# Digital_Input3.net
KiCad netlist of a schematic drawn in Altium Designer
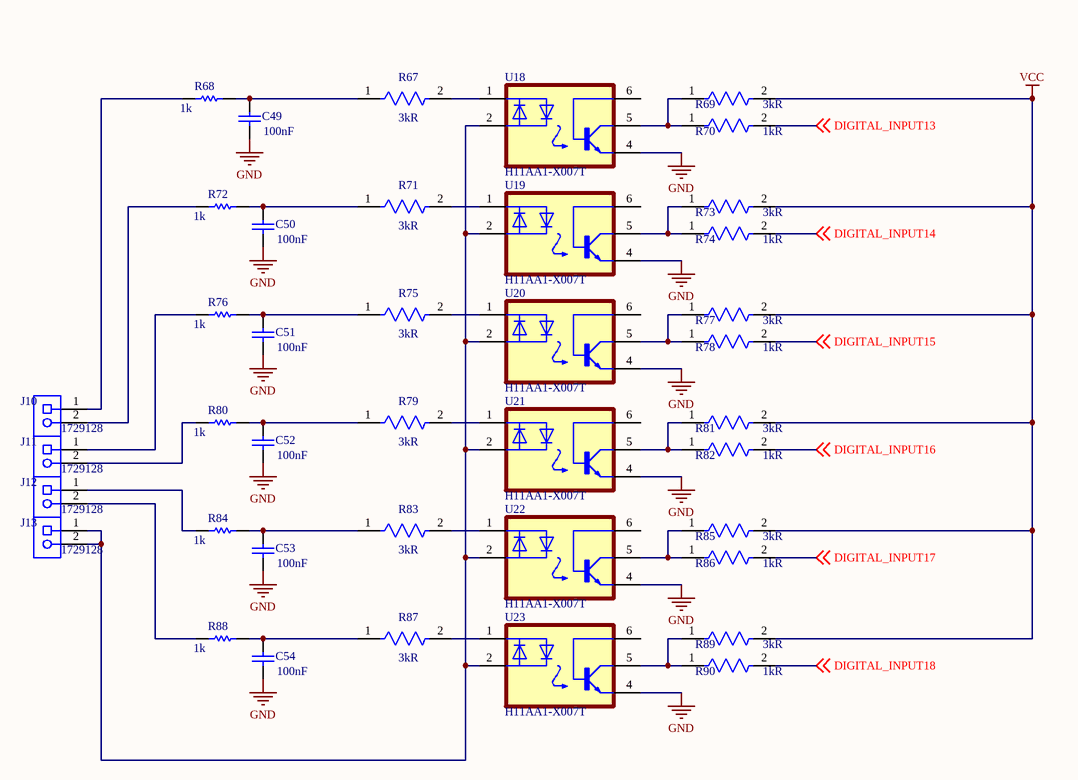
[diagram p0: Digital_Input3.SchDoc]

(export (version "E")
  (design (tool "Eeschema 10.0.6"))
  (components
    (comp (ref "C49")
      (value "100nF")
      (footprint "CAPC1608X87X35NL15T15")
      (fields (field (name "MANUFACTURER") "Kemet") (field (name "PART NUMBER") "C0603T104K3RACTU"))
      (libsource (lib "Altium Content Vault") (part "CAP"))
    )
    (comp (ref "C50")
      (value "100nF")
      (footprint "CAPC1608X87X35NL15T15")
      (fields (field (name "MANUFACTURER") "Kemet") (field (name "PART NUMBER") "C0603T104K3RACTU"))
      (libsource (lib "Altium Content Vault") (part "CAP"))
    )
    (comp (ref "C51")
      (value "100nF")
      (footprint "CAPC1608X87X35NL15T15")
      (fields (field (name "MANUFACTURER") "Kemet") (field (name "PART NUMBER") "C0603T104K3RACTU"))
      (libsource (lib "Altium Content Vault") (part "CAP"))
    )
    (comp (ref "C52")
      (value "100nF")
      (footprint "CAPC1608X87X35NL15T15")
      (fields (field (name "MANUFACTURER") "Kemet") (field (name "PART NUMBER") "C0603T104K3RACTU"))
      (libsource (lib "Altium Content Vault") (part "CAP"))
    )
    (comp (ref "C53")
      (value "100nF")
      (footprint "CAPC1608X87X35NL15T15")
      (fields (field (name "MANUFACTURER") "Kemet") (field (name "PART NUMBER") "C0603T104K3RACTU"))
      (libsource (lib "Altium Content Vault") (part "CAP"))
    )
    (comp (ref "C54")
      (value "100nF")
      (footprint "CAPC1608X87X35NL15T15")
      (fields (field (name "MANUFACTURER") "Kemet") (field (name "PART NUMBER") "C0603T104K3RACTU"))
      (libsource (lib "Altium Content Vault") (part "CAP"))
    )
    (comp (ref "J10")
      (value "1729128")
      (footprint "PHOE-1729128-2_V")
      (description "PCB Terminal Block, 13.5 A, 400 V, 2-Pin THD, RoHS, Bulk")
      (fields (field (name "MANUFACTURER") "Phoenix Contact"))
      (libsource (lib "Altium Content Vault") (part "CN-2P-F-R2"))
    )
    (comp (ref "J11")
      (value "1729128")
      (footprint "PHOE-1729128-2_V")
      (description "PCB Terminal Block, 13.5 A, 400 V, 2-Pin THD, RoHS, Bulk")
      (fields (field (name "MANUFACTURER") "Phoenix Contact"))
      (libsource (lib "Altium Content Vault") (part "CN-2P-F-R2"))
    )
    (comp (ref "J12")
      (value "1729128")
      (footprint "PHOE-1729128-2_V")
      (description "PCB Terminal Block, 13.5 A, 400 V, 2-Pin THD, RoHS, Bulk")
      (fields (field (name "MANUFACTURER") "Phoenix Contact"))
      (libsource (lib "Altium Content Vault") (part "CN-2P-F-R2"))
    )
    (comp (ref "J13")
      (value "1729128")
      (footprint "PHOE-1729128-2_V")
      (description "PCB Terminal Block, 13.5 A, 400 V, 2-Pin THD, RoHS, Bulk")
      (fields (field (name "MANUFACTURER") "Phoenix Contact"))
      (libsource (lib "Altium Content Vault") (part "CN-2P-F-R2"))
    )
    (comp (ref "R67")
      (value "CRCW06033K00FKEA")
      (footprint "FP-CRCW0603-e3-IPC_A")
      (description "RES Thick Film, 3kΩ, 1%, 0.1W, 100ppm/°C, 0603")
      (fields (field (name "RESISTANCE") "3kR") (field (name "TOLERANCE") "1%"))
      (libsource (lib "Altium Content Vault") (part "1029c3af85768c4190bb7ad29bc67b5"))
    )
    (comp (ref "R68")
      (value "1k")
      (footprint "RESC1608X55X25LL10T15")
      (fields (field (name "PART NUMBER") "RT0603DRE071KL") (field (name "MANUFACTURER") "Yageo"))
      (libsource (lib "Altium Content Vault") (part "RES"))
    )
    (comp (ref "R69")
      (value "CRCW06033K00FKEA")
      (footprint "FP-CRCW0603-e3-IPC_A")
      (description "RES Thick Film, 3kΩ, 1%, 0.1W, 100ppm/°C, 0603")
      (fields (field (name "RESISTANCE") "3kR") (field (name "TOLERANCE") "1%"))
      (libsource (lib "Altium Content Vault") (part "1029c3af85768c4190bb7ad29bc67b5"))
    )
    (comp (ref "R70")
      (value "RC0603FR-071KL")
      (footprint "FP-RC0603-0_55-IPC_C")
      (description "RES 1K OHM 1% 1/10W 0603")
      (fields (field (name "RESISTANCE") "1kR") (field (name "TOLERANCE") "1%"))
      (libsource (lib "Altium Content Vault") (part "1029c3af85768c4190bb7ad29bc67b5"))
    )
    (comp (ref "R71")
      (value "CRCW06033K00FKEA")
      (footprint "FP-CRCW0603-e3-IPC_A")
      (description "RES Thick Film, 3kΩ, 1%, 0.1W, 100ppm/°C, 0603")
      (fields (field (name "RESISTANCE") "3kR") (field (name "TOLERANCE") "1%"))
      (libsource (lib "Altium Content Vault") (part "1029c3af85768c4190bb7ad29bc67b5"))
    )
    (comp (ref "R72")
      (value "1k")
      (footprint "RESC1608X55X25LL10T15")
      (fields (field (name "PART NUMBER") "RT0603DRE071KL") (field (name "MANUFACTURER") "Yageo"))
      (libsource (lib "Altium Content Vault") (part "RES"))
    )
    (comp (ref "R73")
      (value "CRCW06033K00FKEA")
      (footprint "FP-CRCW0603-e3-IPC_A")
      (description "RES Thick Film, 3kΩ, 1%, 0.1W, 100ppm/°C, 0603")
      (fields (field (name "RESISTANCE") "3kR") (field (name "TOLERANCE") "1%"))
      (libsource (lib "Altium Content Vault") (part "1029c3af85768c4190bb7ad29bc67b5"))
    )
    (comp (ref "R74")
      (value "RC0603FR-071KL")
      (footprint "FP-RC0603-0_55-IPC_C")
      (description "RES 1K OHM 1% 1/10W 0603")
      (fields (field (name "RESISTANCE") "1kR") (field (name "TOLERANCE") "1%"))
      (libsource (lib "Altium Content Vault") (part "1029c3af85768c4190bb7ad29bc67b5"))
    )
    (comp (ref "R75")
      (value "CRCW06033K00FKEA")
      (footprint "FP-CRCW0603-e3-IPC_A")
      (description "RES Thick Film, 3kΩ, 1%, 0.1W, 100ppm/°C, 0603")
      (fields (field (name "RESISTANCE") "3kR") (field (name "TOLERANCE") "1%"))
      (libsource (lib "Altium Content Vault") (part "1029c3af85768c4190bb7ad29bc67b5"))
    )
    (comp (ref "R76")
      (value "1k")
      (footprint "RESC1608X55X25LL10T15")
      (fields (field (name "PART NUMBER") "RT0603DRE071KL") (field (name "MANUFACTURER") "Yageo"))
      (libsource (lib "Altium Content Vault") (part "RES"))
    )
    (comp (ref "R77")
      (value "CRCW06033K00FKEA")
      (footprint "FP-CRCW0603-e3-IPC_A")
      (description "RES Thick Film, 3kΩ, 1%, 0.1W, 100ppm/°C, 0603")
      (fields (field (name "RESISTANCE") "3kR") (field (name "TOLERANCE") "1%"))
      (libsource (lib "Altium Content Vault") (part "1029c3af85768c4190bb7ad29bc67b5"))
    )
    (comp (ref "R78")
      (value "RC0603FR-071KL")
      (footprint "FP-RC0603-0_55-IPC_C")
      (description "RES 1K OHM 1% 1/10W 0603")
      (fields (field (name "RESISTANCE") "1kR") (field (name "TOLERANCE") "1%"))
      (libsource (lib "Altium Content Vault") (part "1029c3af85768c4190bb7ad29bc67b5"))
    )
    (comp (ref "R79")
      (value "CRCW06033K00FKEA")
      (footprint "FP-CRCW0603-e3-IPC_A")
      (description "RES Thick Film, 3kΩ, 1%, 0.1W, 100ppm/°C, 0603")
      (fields (field (name "RESISTANCE") "3kR") (field (name "TOLERANCE") "1%"))
      (libsource (lib "Altium Content Vault") (part "1029c3af85768c4190bb7ad29bc67b5"))
    )
    (comp (ref "R80")
      (value "1k")
      (footprint "RESC1608X55X25LL10T15")
      (fields (field (name "PART NUMBER") "RT0603DRE071KL") (field (name "MANUFACTURER") "Yageo"))
      (libsource (lib "Altium Content Vault") (part "RES"))
    )
    (comp (ref "R81")
      (value "CRCW06033K00FKEA")
      (footprint "FP-CRCW0603-e3-IPC_A")
      (description "RES Thick Film, 3kΩ, 1%, 0.1W, 100ppm/°C, 0603")
      (fields (field (name "RESISTANCE") "3kR") (field (name "TOLERANCE") "1%"))
      (libsource (lib "Altium Content Vault") (part "1029c3af85768c4190bb7ad29bc67b5"))
    )
    (comp (ref "R82")
      (value "RC0603FR-071KL")
      (footprint "FP-RC0603-0_55-IPC_C")
      (description "RES 1K OHM 1% 1/10W 0603")
      (fields (field (name "RESISTANCE") "1kR") (field (name "TOLERANCE") "1%"))
      (libsource (lib "Altium Content Vault") (part "1029c3af85768c4190bb7ad29bc67b5"))
    )
    (comp (ref "R83")
      (value "CRCW06033K00FKEA")
      (footprint "FP-CRCW0603-e3-IPC_A")
      (description "RES Thick Film, 3kΩ, 1%, 0.1W, 100ppm/°C, 0603")
      (fields (field (name "RESISTANCE") "3kR") (field (name "TOLERANCE") "1%"))
      (libsource (lib "Altium Content Vault") (part "1029c3af85768c4190bb7ad29bc67b5"))
    )
    (comp (ref "R84")
      (value "1k")
      (footprint "RESC1608X55X25LL10T15")
      (fields (field (name "PART NUMBER") "RT0603DRE071KL") (field (name "MANUFACTURER") "Yageo"))
      (libsource (lib "Altium Content Vault") (part "RES"))
    )
    (comp (ref "R85")
      (value "CRCW06033K00FKEA")
      (footprint "FP-CRCW0603-e3-IPC_A")
      (description "RES Thick Film, 3kΩ, 1%, 0.1W, 100ppm/°C, 0603")
      (fields (field (name "RESISTANCE") "3kR") (field (name "TOLERANCE") "1%"))
      (libsource (lib "Altium Content Vault") (part "1029c3af85768c4190bb7ad29bc67b5"))
    )
    (comp (ref "R86")
      (value "RC0603FR-071KL")
      (footprint "FP-RC0603-0_55-IPC_C")
      (description "RES 1K OHM 1% 1/10W 0603")
      (fields (field (name "RESISTANCE") "1kR") (field (name "TOLERANCE") "1%"))
      (libsource (lib "Altium Content Vault") (part "1029c3af85768c4190bb7ad29bc67b5"))
    )
    (comp (ref "R87")
      (value "CRCW06033K00FKEA")
      (footprint "FP-CRCW0603-e3-IPC_A")
      (description "RES Thick Film, 3kΩ, 1%, 0.1W, 100ppm/°C, 0603")
      (fields (field (name "RESISTANCE") "3kR") (field (name "TOLERANCE") "1%"))
      (libsource (lib "Altium Content Vault") (part "1029c3af85768c4190bb7ad29bc67b5"))
    )
    (comp (ref "R88")
      (value "1k")
      (footprint "RESC1608X55X25LL10T15")
      (fields (field (name "PART NUMBER") "RT0603DRE071KL") (field (name "MANUFACTURER") "Yageo"))
      (libsource (lib "Altium Content Vault") (part "RES"))
    )
    (comp (ref "R89")
      (value "CRCW06033K00FKEA")
      (footprint "FP-CRCW0603-e3-IPC_A")
      (description "RES Thick Film, 3kΩ, 1%, 0.1W, 100ppm/°C, 0603")
      (fields (field (name "RESISTANCE") "3kR") (field (name "TOLERANCE") "1%"))
      (libsource (lib "Altium Content Vault") (part "1029c3af85768c4190bb7ad29bc67b5"))
    )
    (comp (ref "R90")
      (value "RC0603FR-071KL")
      (footprint "FP-RC0603-0_55-IPC_C")
      (description "RES 1K OHM 1% 1/10W 0603")
      (fields (field (name "RESISTANCE") "1kR") (field (name "TOLERANCE") "1%"))
      (libsource (lib "Altium Content Vault") (part "1029c3af85768c4190bb7ad29bc67b5"))
    )
    (comp (ref "U18")
      (value "H11AA1-X007T")
      (footprint "SOIC254P1030X460-6N")
      (description "H11AA1 Series Single Channel 30V 5300 Vrms SMT Phototransistor Optocoupler DIP-6")
      (fields (field (name "MF") "Vishay Semiconductor"))
      (libsource (lib "H11AA1-X007T") (part "H11AA1-X007T"))
    )
    (comp (ref "U19")
      (value "H11AA1-X007T")
      (footprint "SOIC254P1030X460-6N")
      (description "H11AA1 Series Single Channel 30V 5300 Vrms SMT Phototransistor Optocoupler DIP-6")
      (fields (field (name "MF") "Vishay Semiconductor"))
      (libsource (lib "H11AA1-X007T") (part "H11AA1-X007T"))
    )
    (comp (ref "U20")
      (value "H11AA1-X007T")
      (footprint "SOIC254P1030X460-6N")
      (description "H11AA1 Series Single Channel 30V 5300 Vrms SMT Phototransistor Optocoupler DIP-6")
      (fields (field (name "MF") "Vishay Semiconductor"))
      (libsource (lib "H11AA1-X007T") (part "H11AA1-X007T"))
    )
    (comp (ref "U21")
      (value "H11AA1-X007T")
      (footprint "SOIC254P1030X460-6N")
      (description "H11AA1 Series Single Channel 30V 5300 Vrms SMT Phototransistor Optocoupler DIP-6")
      (fields (field (name "MF") "Vishay Semiconductor"))
      (libsource (lib "H11AA1-X007T") (part "H11AA1-X007T"))
    )
    (comp (ref "U22")
      (value "H11AA1-X007T")
      (footprint "SOIC254P1030X460-6N")
      (description "H11AA1 Series Single Channel 30V 5300 Vrms SMT Phototransistor Optocoupler DIP-6")
      (fields (field (name "MF") "Vishay Semiconductor"))
      (libsource (lib "H11AA1-X007T") (part "H11AA1-X007T"))
    )
    (comp (ref "U23")
      (value "H11AA1-X007T")
      (footprint "SOIC254P1030X460-6N")
      (description "H11AA1 Series Single Channel 30V 5300 Vrms SMT Phototransistor Optocoupler DIP-6")
      (fields (field (name "MF") "Vishay Semiconductor"))
      (libsource (lib "H11AA1-X007T") (part "H11AA1-X007T"))
    )
  )
  (nets
    (net (code "1") (name "DIGITAL_INPUT13") (class "Default")
      (node (ref "R70") (pin "2") (pinfunction "2_2") (pintype "passive"))
    )
    (net (code "2") (name "DIGITAL_INPUT14") (class "Default")
      (node (ref "R74") (pin "2") (pinfunction "2_2") (pintype "passive"))
    )
    (net (code "3") (name "DIGITAL_INPUT15") (class "Default")
      (node (ref "R78") (pin "2") (pinfunction "2_2") (pintype "passive"))
    )
    (net (code "4") (name "DIGITAL_INPUT16") (class "Default")
      (node (ref "R82") (pin "2") (pinfunction "2_2") (pintype "passive"))
    )
    (net (code "5") (name "DIGITAL_INPUT17") (class "Default")
      (node (ref "R86") (pin "2") (pinfunction "2_2") (pintype "passive"))
    )
    (net (code "6") (name "DIGITAL_INPUT18") (class "Default")
      (node (ref "R90") (pin "2") (pinfunction "2_2") (pintype "passive"))
    )
    (net (code "7") (name "GND") (class "Default")
      (node (ref "C49") (pin "1") (pinfunction "1_1") (pintype "passive"))
      (node (ref "C50") (pin "1") (pinfunction "1_1") (pintype "passive"))
      (node (ref "C51") (pin "1") (pinfunction "1_1") (pintype "passive"))
      (node (ref "C52") (pin "1") (pinfunction "1_1") (pintype "passive"))
      (node (ref "C53") (pin "1") (pinfunction "1_1") (pintype "passive"))
      (node (ref "C54") (pin "1") (pinfunction "1_1") (pintype "passive"))
      (node (ref "U18") (pin "4") (pinfunction "E_4") (pintype "passive"))
      (node (ref "U19") (pin "4") (pinfunction "E_4") (pintype "passive"))
      (node (ref "U20") (pin "4") (pinfunction "E_4") (pintype "passive"))
      (node (ref "U21") (pin "4") (pinfunction "E_4") (pintype "passive"))
      (node (ref "U22") (pin "4") (pinfunction "E_4") (pintype "passive"))
      (node (ref "U23") (pin "4") (pinfunction "E_4") (pintype "passive"))
    )
    (net (code "8") (name "Net-(C49-Pad2)") (class "Default")
      (node (ref "C49") (pin "2") (pinfunction "2_2") (pintype "passive"))
      (node (ref "R67") (pin "1") (pinfunction "1_1") (pintype "passive"))
      (node (ref "R68") (pin "2") (pinfunction "2_2") (pintype "passive"))
    )
    (net (code "9") (name "Net-(C50-Pad2)") (class "Default")
      (node (ref "C50") (pin "2") (pinfunction "2_2") (pintype "passive"))
      (node (ref "R71") (pin "1") (pinfunction "1_1") (pintype "passive"))
      (node (ref "R72") (pin "2") (pinfunction "2_2") (pintype "passive"))
    )
    (net (code "10") (name "Net-(C51-Pad2)") (class "Default")
      (node (ref "C51") (pin "2") (pinfunction "2_2") (pintype "passive"))
      (node (ref "R75") (pin "1") (pinfunction "1_1") (pintype "passive"))
      (node (ref "R76") (pin "2") (pinfunction "2_2") (pintype "passive"))
    )
    (net (code "11") (name "Net-(C52-Pad2)") (class "Default")
      (node (ref "C52") (pin "2") (pinfunction "2_2") (pintype "passive"))
      (node (ref "R79") (pin "1") (pinfunction "1_1") (pintype "passive"))
      (node (ref "R80") (pin "2") (pinfunction "2_2") (pintype "passive"))
    )
    (net (code "12") (name "Net-(C53-Pad2)") (class "Default")
      (node (ref "C53") (pin "2") (pinfunction "2_2") (pintype "passive"))
      (node (ref "R83") (pin "1") (pinfunction "1_1") (pintype "passive"))
      (node (ref "R84") (pin "2") (pinfunction "2_2") (pintype "passive"))
    )
    (net (code "13") (name "Net-(C54-Pad2)") (class "Default")
      (node (ref "C54") (pin "2") (pinfunction "2_2") (pintype "passive"))
      (node (ref "R87") (pin "1") (pinfunction "1_1") (pintype "passive"))
      (node (ref "R88") (pin "2") (pinfunction "2_2") (pintype "passive"))
    )
    (net (code "14") (name "Net-(J10-Pad1)") (class "Default")
      (node (ref "J10") (pin "1") (pinfunction "1_1") (pintype "passive"))
      (node (ref "R68") (pin "1") (pinfunction "1_1") (pintype "passive"))
    )
    (net (code "15") (name "Net-(J10-Pad2)") (class "Default")
      (node (ref "J10") (pin "2") (pinfunction "2_2") (pintype "passive"))
      (node (ref "R72") (pin "1") (pinfunction "1_1") (pintype "passive"))
    )
    (net (code "16") (name "Net-(J11-Pad1)") (class "Default")
      (node (ref "J11") (pin "1") (pinfunction "1_1") (pintype "passive"))
      (node (ref "R76") (pin "1") (pinfunction "1_1") (pintype "passive"))
    )
    (net (code "17") (name "Net-(J11-Pad2)") (class "Default")
      (node (ref "J11") (pin "2") (pinfunction "2_2") (pintype "passive"))
      (node (ref "R80") (pin "1") (pinfunction "1_1") (pintype "passive"))
    )
    (net (code "18") (name "Net-(J12-Pad1)") (class "Default")
      (node (ref "J12") (pin "1") (pinfunction "1_1") (pintype "passive"))
      (node (ref "R84") (pin "1") (pinfunction "1_1") (pintype "passive"))
    )
    (net (code "19") (name "Net-(J12-Pad2)") (class "Default")
      (node (ref "J12") (pin "2") (pinfunction "2_2") (pintype "passive"))
      (node (ref "R88") (pin "1") (pinfunction "1_1") (pintype "passive"))
    )
    (net (code "20") (name "Net-(U18-A{slash}C)") (class "Default")
      (node (ref "R67") (pin "2") (pinfunction "2_2") (pintype "passive"))
      (node (ref "U18") (pin "1") (pinfunction "A/C_1") (pintype "passive"))
    )
    (net (code "21") (name "Net-(U18-C)") (class "Default")
      (node (ref "R69") (pin "1") (pinfunction "1_1") (pintype "passive"))
      (node (ref "R70") (pin "1") (pinfunction "1_1") (pintype "passive"))
      (node (ref "U18") (pin "5") (pinfunction "C_5") (pintype "passive"))
    )
    (net (code "22") (name "Net-(U18-C{slash}A)") (class "Default")
      (node (ref "J13") (pin "1") (pinfunction "1_1") (pintype "passive"))
      (node (ref "J13") (pin "2") (pinfunction "2_2") (pintype "passive"))
      (node (ref "U18") (pin "2") (pinfunction "C/A_2") (pintype "passive"))
      (node (ref "U19") (pin "2") (pinfunction "C/A_2") (pintype "passive"))
      (node (ref "U20") (pin "2") (pinfunction "C/A_2") (pintype "passive"))
      (node (ref "U21") (pin "2") (pinfunction "C/A_2") (pintype "passive"))
      (node (ref "U22") (pin "2") (pinfunction "C/A_2") (pintype "passive"))
      (node (ref "U23") (pin "2") (pinfunction "C/A_2") (pintype "passive"))
    )
    (net (code "23") (name "Net-(U19-A{slash}C)") (class "Default")
      (node (ref "R71") (pin "2") (pinfunction "2_2") (pintype "passive"))
      (node (ref "U19") (pin "1") (pinfunction "A/C_1") (pintype "passive"))
    )
    (net (code "24") (name "Net-(U19-C)") (class "Default")
      (node (ref "R73") (pin "1") (pinfunction "1_1") (pintype "passive"))
      (node (ref "R74") (pin "1") (pinfunction "1_1") (pintype "passive"))
      (node (ref "U19") (pin "5") (pinfunction "C_5") (pintype "passive"))
    )
    (net (code "25") (name "Net-(U20-A{slash}C)") (class "Default")
      (node (ref "R75") (pin "2") (pinfunction "2_2") (pintype "passive"))
      (node (ref "U20") (pin "1") (pinfunction "A/C_1") (pintype "passive"))
    )
    (net (code "26") (name "Net-(U20-C)") (class "Default")
      (node (ref "R77") (pin "1") (pinfunction "1_1") (pintype "passive"))
      (node (ref "R78") (pin "1") (pinfunction "1_1") (pintype "passive"))
      (node (ref "U20") (pin "5") (pinfunction "C_5") (pintype "passive"))
    )
    (net (code "27") (name "Net-(U21-A{slash}C)") (class "Default")
      (node (ref "R79") (pin "2") (pinfunction "2_2") (pintype "passive"))
      (node (ref "U21") (pin "1") (pinfunction "A/C_1") (pintype "passive"))
    )
    (net (code "28") (name "Net-(U21-C)") (class "Default")
      (node (ref "R81") (pin "1") (pinfunction "1_1") (pintype "passive"))
      (node (ref "R82") (pin "1") (pinfunction "1_1") (pintype "passive"))
      (node (ref "U21") (pin "5") (pinfunction "C_5") (pintype "passive"))
    )
    (net (code "29") (name "Net-(U22-A{slash}C)") (class "Default")
      (node (ref "R83") (pin "2") (pinfunction "2_2") (pintype "passive"))
      (node (ref "U22") (pin "1") (pinfunction "A/C_1") (pintype "passive"))
    )
    (net (code "30") (name "Net-(U22-C)") (class "Default")
      (node (ref "R85") (pin "1") (pinfunction "1_1") (pintype "passive"))
      (node (ref "R86") (pin "1") (pinfunction "1_1") (pintype "passive"))
      (node (ref "U22") (pin "5") (pinfunction "C_5") (pintype "passive"))
    )
    (net (code "31") (name "Net-(U23-A{slash}C)") (class "Default")
      (node (ref "R87") (pin "2") (pinfunction "2_2") (pintype "passive"))
      (node (ref "U23") (pin "1") (pinfunction "A/C_1") (pintype "passive"))
    )
    (net (code "32") (name "Net-(U23-C)") (class "Default")
      (node (ref "R89") (pin "1") (pinfunction "1_1") (pintype "passive"))
      (node (ref "R90") (pin "1") (pinfunction "1_1") (pintype "passive"))
      (node (ref "U23") (pin "5") (pinfunction "C_5") (pintype "passive"))
    )
    (net (code "33") (name "VCC") (class "Default")
      (node (ref "R69") (pin "2") (pinfunction "2_2") (pintype "passive"))
      (node (ref "R73") (pin "2") (pinfunction "2_2") (pintype "passive"))
      (node (ref "R77") (pin "2") (pinfunction "2_2") (pintype "passive"))
      (node (ref "R81") (pin "2") (pinfunction "2_2") (pintype "passive"))
      (node (ref "R85") (pin "2") (pinfunction "2_2") (pintype "passive"))
      (node (ref "R89") (pin "2") (pinfunction "2_2") (pintype "passive"))
    )
    (net (code "34") (name "unconnected-(U18-B-Pad6)") (class "Default")
      (node (ref "U18") (pin "6") (pinfunction "B_6") (pintype "passive"))
    )
    (net (code "35") (name "unconnected-(U19-B-Pad6)") (class "Default")
      (node (ref "U19") (pin "6") (pinfunction "B_6") (pintype "passive"))
    )
    (net (code "36") (name "unconnected-(U20-B-Pad6)") (class "Default")
      (node (ref "U20") (pin "6") (pinfunction "B_6") (pintype "passive"))
    )
    (net (code "37") (name "unconnected-(U21-B-Pad6)") (class "Default")
      (node (ref "U21") (pin "6") (pinfunction "B_6") (pintype "passive"))
    )
    (net (code "38") (name "unconnected-(U22-B-Pad6)") (class "Default")
      (node (ref "U22") (pin "6") (pinfunction "B_6") (pintype "passive"))
    )
    (net (code "39") (name "unconnected-(U23-B-Pad6)") (class "Default")
      (node (ref "U23") (pin "6") (pinfunction "B_6") (pintype "passive"))
    )
  )
)
